# VNT_Controller_Schematic.net
KiCad netlist of a schematic drawn in EAGLE
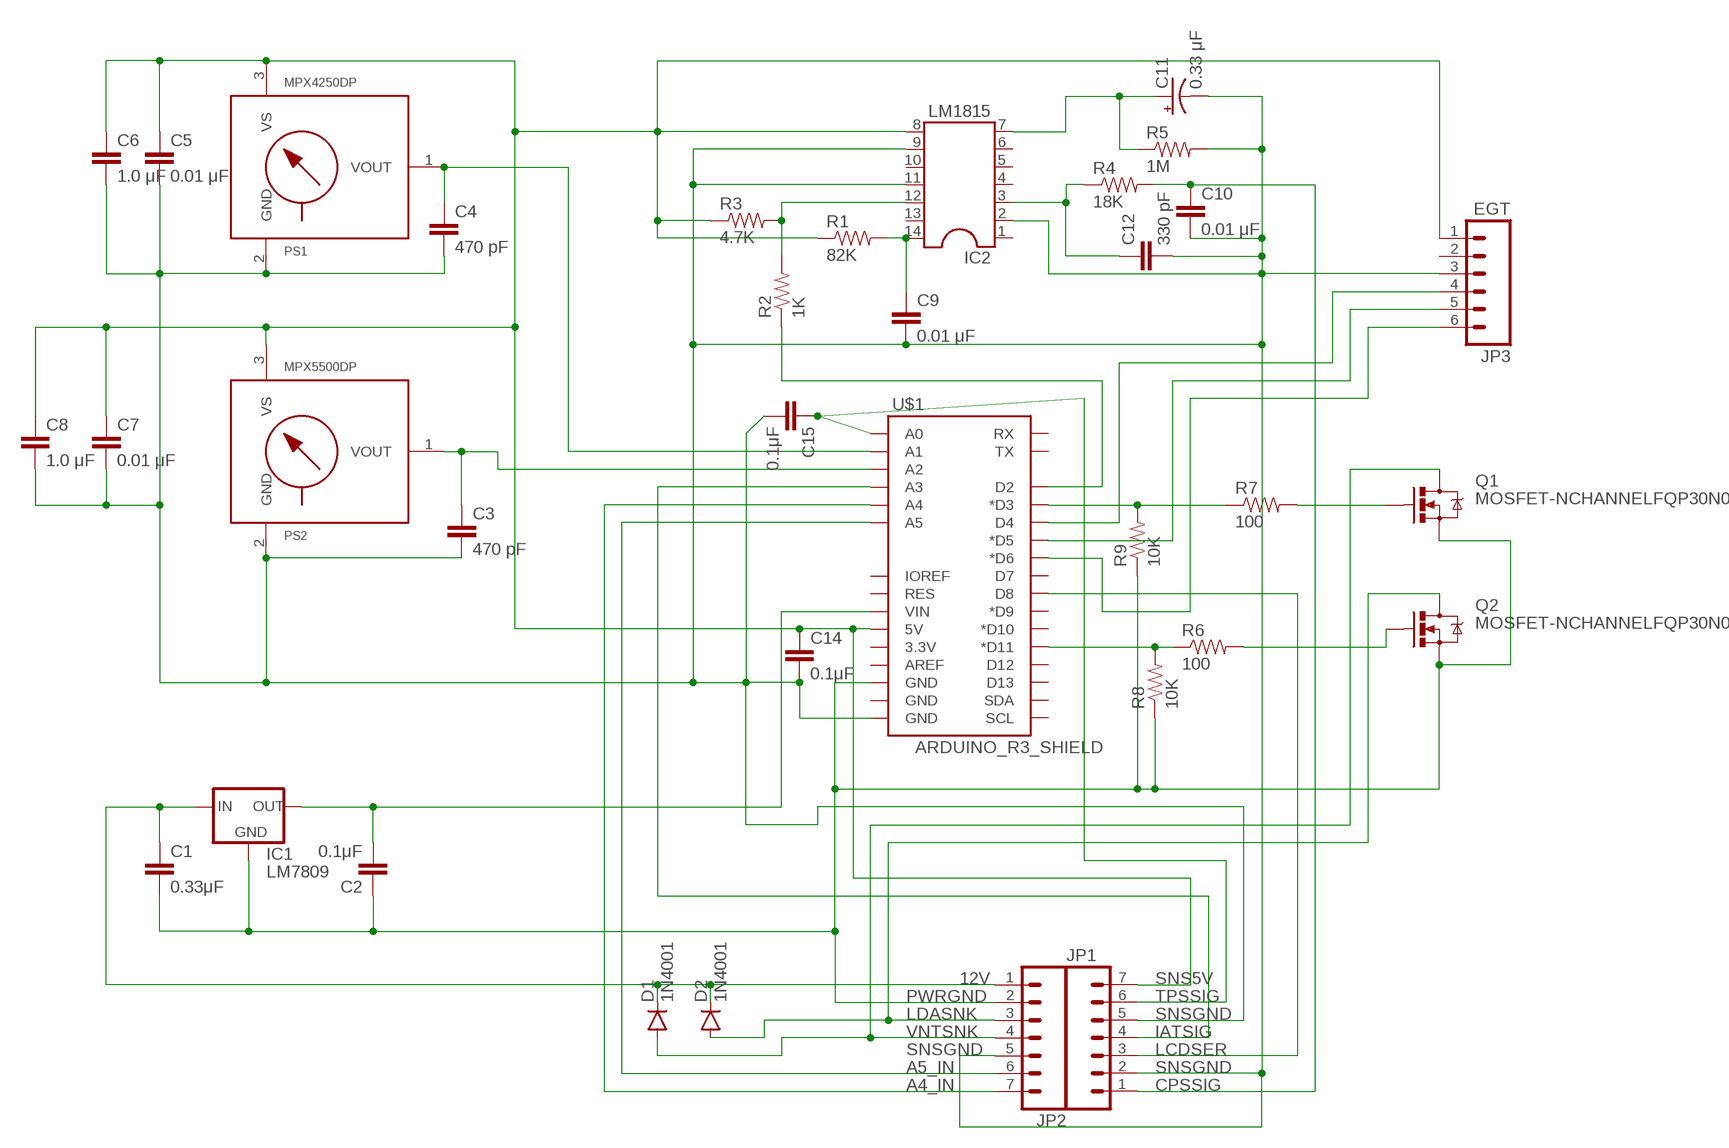
[diagram p0: schematic, sheet 1]

(export (version "E")
  (design (tool "Eeschema 10.0.6"))
  (components
    (comp (ref "C1")
      (value "0.33μF")
      (footprint "eagle-import:CAP-PTH-SMALL")
      (libsource (lib "eagle-import") (part "CAPPTH"))
    )
    (comp (ref "C2")
      (value "0.1μF")
      (footprint "eagle-import:CAP-PTH-SMALL")
      (libsource (lib "eagle-import") (part "CAPPTH"))
    )
    (comp (ref "C3")
      (value "470 pF")
      (footprint "eagle-import:CAP-PTH-SMALL")
      (libsource (lib "eagle-import") (part "CAPPTH"))
    )
    (comp (ref "C4")
      (value "470 pF")
      (footprint "eagle-import:CAP-PTH-SMALL")
      (libsource (lib "eagle-import") (part "CAPPTH"))
    )
    (comp (ref "C5")
      (value "0.01 μF")
      (footprint "eagle-import:CAP-PTH-SMALL")
      (libsource (lib "eagle-import") (part "CAPPTH"))
    )
    (comp (ref "C6")
      (value "1.0 μF")
      (footprint "eagle-import:CAP-PTH-SMALL")
      (libsource (lib "eagle-import") (part "CAPPTH"))
    )
    (comp (ref "C7")
      (value "0.01 μF")
      (footprint "eagle-import:CAP-PTH-SMALL")
      (libsource (lib "eagle-import") (part "CAPPTH"))
    )
    (comp (ref "C8")
      (value "1.0 μF")
      (footprint "eagle-import:CAP-PTH-SMALL")
      (libsource (lib "eagle-import") (part "CAPPTH"))
    )
    (comp (ref "C9")
      (value "0.01 μF")
      (footprint "eagle-import:CAP-PTH-SMALL")
      (libsource (lib "eagle-import") (part "CAPPTH"))
    )
    (comp (ref "C10")
      (value "0.01 μF")
      (footprint "eagle-import:CAP-PTH-SMALL")
      (libsource (lib "eagle-import") (part "CAPPTH"))
    )
    (comp (ref "C11")
      (value "0.33 μF")
      (footprint "eagle-import:CPOL-RADIAL-10UF-25V")
      (libsource (lib "eagle-import") (part "CAP_POLPTH2"))
    )
    (comp (ref "C12")
      (value "330 pF")
      (footprint "eagle-import:CAP-PTH-SMALL")
      (libsource (lib "eagle-import") (part "CAPPTH"))
    )
    (comp (ref "C14")
      (value "0.1μF")
      (footprint "eagle-import:CAP-PTH-SMALL")
      (libsource (lib "eagle-import") (part "CAPPTH"))
    )
    (comp (ref "C15")
      (value "0.1μF")
      (footprint "eagle-import:CAP-PTH-SMALL")
      (libsource (lib "eagle-import") (part "CAPPTH"))
    )
    (comp (ref "D1")
      (value "1N4001")
      (footprint "eagle-import:DIODE-1N4001")
      (libsource (lib "eagle-import") (part "DIODEPTH"))
    )
    (comp (ref "D2")
      (value "1N4001")
      (footprint "eagle-import:DIODE-1N4001")
      (libsource (lib "eagle-import") (part "DIODEPTH"))
    )
    (comp (ref "IC1")
      (value "LM7809")
      (footprint "eagle-import:TO220-IGO")
      (libsource (lib "eagle-import") (part "V_REG_78XXSINK"))
    )
    (comp (ref "IC2")
      (value "LM1815")
      (footprint "eagle-import:SOCKET-14")
      (libsource (lib "eagle-import") (part "DIL14S"))
    )
    (comp (ref "JP1")
      (value "M07LOCK_LONGPADS")
      (footprint "eagle-import:1X07_LOCK_LONGPADS")
      (libsource (lib "eagle-import") (part "M07LOCK_LONGPADS"))
    )
    (comp (ref "JP2")
      (value "M07LOCK_LONGPADS")
      (footprint "eagle-import:1X07_LOCK_LONGPADS")
      (libsource (lib "eagle-import") (part "M07LOCK_LONGPADS"))
    )
    (comp (ref "JP3")
      (value "EGT")
      (footprint "eagle-import:1X06-SIP_LOCK")
      (libsource (lib "eagle-import") (part "M06SIP_LOCK"))
    )
    (comp (ref "PS1")
      (value "MPX4250DP")
      (footprint "eagle-import:867C-H")
      (libsource (lib "eagle-import") (part "MPX-867C-H"))
    )
    (comp (ref "PS2")
      (value "MPX5500DP")
      (footprint "eagle-import:867C-H")
      (libsource (lib "eagle-import") (part "MPX-867C-H"))
    )
    (comp (ref "Q1")
      (value "MOSFET-NCHANNELFQP30N06L")
      (footprint "eagle-import:TO220V")
      (libsource (lib "eagle-import") (part "MOSFET-NCHANNELFQP30N06L"))
    )
    (comp (ref "Q2")
      (value "MOSFET-NCHANNELFQP30N06L")
      (footprint "eagle-import:TO220V")
      (libsource (lib "eagle-import") (part "MOSFET-NCHANNELFQP30N06L"))
    )
    (comp (ref "R1")
      (value "82K")
      (footprint "eagle-import:AXIAL-0.1")
      (libsource (lib "eagle-import") (part "RESISTORPTH-1/4W-VERT"))
    )
    (comp (ref "R2")
      (value "1K")
      (footprint "eagle-import:AXIAL-0.1")
      (libsource (lib "eagle-import") (part "RESISTORPTH-1/4W-VERT"))
    )
    (comp (ref "R3")
      (value "4.7K")
      (footprint "eagle-import:AXIAL-0.1")
      (libsource (lib "eagle-import") (part "RESISTORPTH-1/4W-VERT"))
    )
    (comp (ref "R4")
      (value "18K")
      (footprint "eagle-import:AXIAL-0.1")
      (libsource (lib "eagle-import") (part "RESISTORPTH-1/4W-VERT"))
    )
    (comp (ref "R5")
      (value "1M")
      (footprint "eagle-import:AXIAL-0.1")
      (libsource (lib "eagle-import") (part "RESISTORPTH-1/4W-VERT"))
    )
    (comp (ref "R6")
      (value "100")
      (footprint "eagle-import:AXIAL-0.1")
      (libsource (lib "eagle-import") (part "RESISTORPTH-1/4W-VERT"))
    )
    (comp (ref "R7")
      (value "100")
      (footprint "eagle-import:AXIAL-0.1")
      (libsource (lib "eagle-import") (part "RESISTORPTH-1/4W-VERT"))
    )
    (comp (ref "R8")
      (value "10K")
      (footprint "eagle-import:AXIAL-0.1")
      (libsource (lib "eagle-import") (part "RESISTORPTH-1/4W-VERT"))
    )
    (comp (ref "R9")
      (value "10K")
      (footprint "eagle-import:AXIAL-0.1")
      (libsource (lib "eagle-import") (part "RESISTORPTH-1/4W-VERT"))
    )
    (comp (ref "U$1")
      (value "ARDUINO_R3_SHIELD")
      (footprint "eagle-import:UNO_R3_SHIELD")
      (libsource (lib "eagle-import") (part "ARDUINO_R3_SHIELD"))
    )
  )
  (nets
    (net (code "1") (name "/12V") (class "Default")
      (node (ref "C1") (pin "1") (pinfunction "1_1") (pintype "passive"))
      (node (ref "D1") (pin "C") (pinfunction "C_C") (pintype "passive"))
      (node (ref "D2") (pin "C") (pinfunction "C_C") (pintype "passive"))
      (node (ref "IC1") (pin "IN") (pinfunction "IN_IN") (pintype "input"))
      (node (ref "JP2") (pin "1") (pinfunction "1_1") (pintype "passive"))
    )
    (net (code "2") (name "/A4_IN") (class "Default")
      (node (ref "JP2") (pin "7") (pinfunction "7_7") (pintype "passive"))
      (node (ref "U$1") (pin "A4") (pinfunction "A4_A4") (pintype "bidirectional"))
    )
    (net (code "3") (name "/A5_IN") (class "Default")
      (node (ref "JP2") (pin "6") (pinfunction "6_6") (pintype "passive"))
      (node (ref "U$1") (pin "A5") (pinfunction "A5_A5") (pintype "bidirectional"))
    )
    (net (code "4") (name "/CPSSIG") (class "Default")
      (node (ref "C10") (pin "1") (pinfunction "1_1") (pintype "passive"))
      (node (ref "JP1") (pin "1") (pinfunction "1_1") (pintype "passive"))
      (node (ref "R4") (pin "P$2") (pinfunction "2_P$2") (pintype "passive"))
    )
    (net (code "5") (name "/IATSIG") (class "Default")
      (node (ref "JP1") (pin "4") (pinfunction "4_4") (pintype "passive"))
      (node (ref "U$1") (pin "A3") (pinfunction "A3_A3") (pintype "bidirectional"))
    )
    (net (code "6") (name "/LCDSER") (class "Default")
      (node (ref "JP1") (pin "3") (pinfunction "3_3") (pintype "passive"))
      (node (ref "U$1") (pin "D8") (pinfunction "D8_D8") (pintype "bidirectional"))
    )
    (net (code "7") (name "/LDASNK") (class "Default")
      (node (ref "D2") (pin "A") (pinfunction "A_A") (pintype "passive"))
      (node (ref "JP2") (pin "3") (pinfunction "3_3") (pintype "passive"))
      (node (ref "Q2") (pin "2") (pinfunction "D_2") (pintype "passive"))
    )
    (net (code "8") (name "/PWRGND") (class "Default")
      (node (ref "C1") (pin "2") (pinfunction "2_2") (pintype "passive"))
      (node (ref "C2") (pin "1") (pinfunction "1_1") (pintype "passive"))
      (node (ref "IC1") (pin "GND") (pinfunction "GND_GND") (pintype "input"))
      (node (ref "JP2") (pin "2") (pinfunction "2_2") (pintype "passive"))
      (node (ref "Q1") (pin "3") (pinfunction "S_3") (pintype "passive"))
      (node (ref "Q2") (pin "3") (pinfunction "S_3") (pintype "passive"))
      (node (ref "R8") (pin "P$1") (pinfunction "1_P$1") (pintype "passive"))
      (node (ref "R9") (pin "P$1") (pinfunction "1_P$1") (pintype "passive"))
      (node (ref "U$1") (pin "GND@2") (pinfunction "GND_GND@2") (pintype "bidirectional"))
    )
    (net (code "9") (name "/SNS5V") (class "Default")
      (node (ref "C14") (pin "1") (pinfunction "1_1") (pintype "passive"))
      (node (ref "C5") (pin "1") (pinfunction "1_1") (pintype "passive"))
      (node (ref "C6") (pin "1") (pinfunction "1_1") (pintype "passive"))
      (node (ref "C7") (pin "1") (pinfunction "1_1") (pintype "passive"))
      (node (ref "C8") (pin "1") (pinfunction "1_1") (pintype "passive"))
      (node (ref "IC2") (pin "8") (pinfunction "8_8") (pintype "passive"))
      (node (ref "JP1") (pin "7") (pinfunction "7_7") (pintype "passive"))
      (node (ref "JP3") (pin "1") (pinfunction "1_1") (pintype "passive"))
      (node (ref "PS1") (pin "3") (pinfunction "VS_3") (pintype "power_in"))
      (node (ref "PS2") (pin "3") (pinfunction "VS_3") (pintype "power_in"))
      (node (ref "R1") (pin "P$1") (pinfunction "1_P$1") (pintype "passive"))
      (node (ref "R3") (pin "P$1") (pinfunction "1_P$1") (pintype "passive"))
      (node (ref "U$1") (pin "5V") (pinfunction "5V_5V") (pintype "bidirectional"))
    )
    (net (code "10") (name "/SNSGND") (class "Default")
      (node (ref "C10") (pin "2") (pinfunction "2_2") (pintype "passive"))
      (node (ref "C11") (pin "2") (pinfunction "-_2") (pintype "passive"))
      (node (ref "C12") (pin "2") (pinfunction "2_2") (pintype "passive"))
      (node (ref "C14") (pin "2") (pinfunction "2_2") (pintype "passive"))
      (node (ref "C15") (pin "2") (pinfunction "2_2") (pintype "passive"))
      (node (ref "C3") (pin "2") (pinfunction "2_2") (pintype "passive"))
      (node (ref "C4") (pin "2") (pinfunction "2_2") (pintype "passive"))
      (node (ref "C5") (pin "2") (pinfunction "2_2") (pintype "passive"))
      (node (ref "C6") (pin "2") (pinfunction "2_2") (pintype "passive"))
      (node (ref "C7") (pin "2") (pinfunction "2_2") (pintype "passive"))
      (node (ref "C8") (pin "2") (pinfunction "2_2") (pintype "passive"))
      (node (ref "C9") (pin "2") (pinfunction "2_2") (pintype "passive"))
      (node (ref "IC2") (pin "11") (pinfunction "11_11") (pintype "passive"))
      (node (ref "IC2") (pin "2") (pinfunction "2_2") (pintype "passive"))
      (node (ref "IC2") (pin "9") (pinfunction "9_9") (pintype "passive"))
      (node (ref "JP1") (pin "2") (pinfunction "2_2") (pintype "passive"))
      (node (ref "JP1") (pin "5") (pinfunction "5_5") (pintype "passive"))
      (node (ref "JP2") (pin "5") (pinfunction "5_5") (pintype "passive"))
      (node (ref "JP3") (pin "3") (pinfunction "3_3") (pintype "passive"))
      (node (ref "PS1") (pin "2") (pinfunction "GND_2") (pintype "power_in"))
      (node (ref "PS2") (pin "2") (pinfunction "GND_2") (pintype "power_in"))
      (node (ref "R5") (pin "P$2") (pinfunction "2_P$2") (pintype "passive"))
      (node (ref "U$1") (pin "GND@0") (pinfunction "GND_GND@0") (pintype "bidirectional"))
    )
    (net (code "11") (name "/TPSSIG") (class "Default")
      (node (ref "C15") (pin "1") (pinfunction "1_1") (pintype "passive"))
      (node (ref "JP1") (pin "6") (pinfunction "6_6") (pintype "passive"))
      (node (ref "U$1") (pin "A0") (pinfunction "A0_A0") (pintype "bidirectional"))
    )
    (net (code "12") (name "/VNTSNK") (class "Default")
      (node (ref "D1") (pin "A") (pinfunction "A_A") (pintype "passive"))
      (node (ref "JP2") (pin "4") (pinfunction "4_4") (pintype "passive"))
      (node (ref "Q1") (pin "2") (pinfunction "D_2") (pintype "passive"))
    )
    (net (code "13") (name "Net-(C2-Pad2)") (class "Default")
      (node (ref "C2") (pin "2") (pinfunction "2_2") (pintype "passive"))
      (node (ref "IC1") (pin "OUT") (pinfunction "OUT_OUT") (pintype "output"))
      (node (ref "U$1") (pin "VIN") (pinfunction "VIN_VIN") (pintype "bidirectional"))
    )
    (net (code "14") (name "Net-(C11-+)") (class "Default")
      (node (ref "C11") (pin "1") (pinfunction "+_1") (pintype "passive"))
      (node (ref "IC2") (pin "7") (pinfunction "7_7") (pintype "passive"))
      (node (ref "R5") (pin "P$1") (pinfunction "1_P$1") (pintype "passive"))
    )
    (net (code "15") (name "Net-(JP3-Pad4)") (class "Default")
      (node (ref "JP3") (pin "4") (pinfunction "4_4") (pintype "passive"))
      (node (ref "U$1") (pin "D4") (pinfunction "D4_D4") (pintype "bidirectional"))
    )
    (net (code "16") (name "Net-(PS1-VOUT)") (class "Default")
      (node (ref "C4") (pin "1") (pinfunction "1_1") (pintype "passive"))
      (node (ref "PS1") (pin "1") (pinfunction "VOUT_1") (pintype "output"))
      (node (ref "U$1") (pin "A1") (pinfunction "A1_A1") (pintype "bidirectional"))
    )
    (net (code "17") (name "Net-(PS2-VOUT)") (class "Default")
      (node (ref "C3") (pin "1") (pinfunction "1_1") (pintype "passive"))
      (node (ref "PS2") (pin "1") (pinfunction "VOUT_1") (pintype "output"))
      (node (ref "U$1") (pin "A2") (pinfunction "A2_A2") (pintype "bidirectional"))
    )
    (net (code "18") (name "Net-(Q1-G)") (class "Default")
      (node (ref "Q1") (pin "1") (pinfunction "G_1") (pintype "passive"))
      (node (ref "R7") (pin "P$2") (pinfunction "2_P$2") (pintype "passive"))
    )
    (net (code "19") (name "Net-(Q2-G)") (class "Default")
      (node (ref "Q2") (pin "1") (pinfunction "G_1") (pintype "passive"))
      (node (ref "R6") (pin "P$2") (pinfunction "2_P$2") (pintype "passive"))
    )
    (net (code "20") (name "Net-(R1-2)") (class "Default")
      (node (ref "C9") (pin "1") (pinfunction "1_1") (pintype "passive"))
      (node (ref "IC2") (pin "14") (pinfunction "14_14") (pintype "passive"))
      (node (ref "R1") (pin "P$2") (pinfunction "2_P$2") (pintype "passive"))
    )
    (net (code "21") (name "Net-(R2-1)") (class "Default")
      (node (ref "R2") (pin "P$1") (pinfunction "1_P$1") (pintype "passive"))
      (node (ref "U$1") (pin "D2") (pinfunction "D2_D2") (pintype "bidirectional"))
    )
    (net (code "22") (name "Net-(R2-2)") (class "Default")
      (node (ref "IC2") (pin "12") (pinfunction "12_12") (pintype "passive"))
      (node (ref "R2") (pin "P$2") (pinfunction "2_P$2") (pintype "passive"))
      (node (ref "R3") (pin "P$2") (pinfunction "2_P$2") (pintype "passive"))
    )
    (net (code "23") (name "Net-(R4-1)") (class "Default")
      (node (ref "C12") (pin "1") (pinfunction "1_1") (pintype "passive"))
      (node (ref "IC2") (pin "3") (pinfunction "3_3") (pintype "passive"))
      (node (ref "R4") (pin "P$1") (pinfunction "1_P$1") (pintype "passive"))
    )
    (net (code "24") (name "Net-(R6-1)") (class "Default")
      (node (ref "R6") (pin "P$1") (pinfunction "1_P$1") (pintype "passive"))
      (node (ref "R8") (pin "P$2") (pinfunction "2_P$2") (pintype "passive"))
      (node (ref "U$1") (pin "D11") (pinfunction "*D11_D11") (pintype "bidirectional"))
    )
    (net (code "25") (name "Net-(R7-1)") (class "Default")
      (node (ref "R7") (pin "P$1") (pinfunction "1_P$1") (pintype "passive"))
      (node (ref "R9") (pin "P$2") (pinfunction "2_P$2") (pintype "passive"))
      (node (ref "U$1") (pin "D3") (pinfunction "*D3_D3") (pintype "bidirectional"))
    )
    (net (code "26") (name "Net-(U$1-*D5)") (class "Default")
      (node (ref "JP3") (pin "5") (pinfunction "5_5") (pintype "passive"))
      (node (ref "U$1") (pin "D5") (pinfunction "*D5_D5") (pintype "bidirectional"))
    )
    (net (code "27") (name "Net-(U$1-*D6)") (class "Default")
      (node (ref "JP3") (pin "6") (pinfunction "6_6") (pintype "passive"))
      (node (ref "U$1") (pin "D6") (pinfunction "*D6_D6") (pintype "bidirectional"))
    )
    (net (code "28") (name "unconnected-(IC2-Pad1)") (class "Default")
      (node (ref "IC2") (pin "1") (pinfunction "1_1") (pintype "passive"))
    )
    (net (code "29") (name "unconnected-(IC2-Pad4)") (class "Default")
      (node (ref "IC2") (pin "4") (pinfunction "4_4") (pintype "passive"))
    )
    (net (code "30") (name "unconnected-(IC2-Pad5)") (class "Default")
      (node (ref "IC2") (pin "5") (pinfunction "5_5") (pintype "passive"))
    )
    (net (code "31") (name "unconnected-(IC2-Pad6)") (class "Default")
      (node (ref "IC2") (pin "6") (pinfunction "6_6") (pintype "passive"))
    )
    (net (code "32") (name "unconnected-(IC2-Pad10)") (class "Default")
      (node (ref "IC2") (pin "10") (pinfunction "10_10") (pintype "passive"))
    )
    (net (code "33") (name "unconnected-(IC2-Pad13)") (class "Default")
      (node (ref "IC2") (pin "13") (pinfunction "13_13") (pintype "passive"))
    )
    (net (code "34") (name "unconnected-(JP3-Pad2)") (class "Default")
      (node (ref "JP3") (pin "2") (pinfunction "2_2") (pintype "passive"))
    )
    (net (code "35") (name "unconnected-(PS1-NC-Pad4)") (class "Default")
      (node (ref "PS1") (pin "4") (pinfunction "NC_4") (pintype "no_connect"))
    )
    (net (code "36") (name "unconnected-(PS1-NC-Pad5)") (class "Default")
      (node (ref "PS1") (pin "5") (pinfunction "NC_5") (pintype "no_connect"))
    )
    (net (code "37") (name "unconnected-(PS1-NC-Pad6)") (class "Default")
      (node (ref "PS1") (pin "6") (pinfunction "NC_6") (pintype "no_connect"))
    )
    (net (code "38") (name "unconnected-(PS2-NC-Pad4)") (class "Default")
      (node (ref "PS2") (pin "4") (pinfunction "NC_4") (pintype "no_connect"))
    )
    (net (code "39") (name "unconnected-(PS2-NC-Pad5)") (class "Default")
      (node (ref "PS2") (pin "5") (pinfunction "NC_5") (pintype "no_connect"))
    )
    (net (code "40") (name "unconnected-(PS2-NC-Pad6)") (class "Default")
      (node (ref "PS2") (pin "6") (pinfunction "NC_6") (pintype "no_connect"))
    )
    (net (code "41") (name "unconnected-(U$1-*D9-PadD9)") (class "Default")
      (node (ref "U$1") (pin "D9") (pinfunction "*D9_D9") (pintype "bidirectional"))
    )
    (net (code "42") (name "unconnected-(U$1-*D10-PadD10)") (class "Default")
      (node (ref "U$1") (pin "D10") (pinfunction "*D10_D10") (pintype "bidirectional"))
    )
    (net (code "43") (name "unconnected-(U$1-GND-PadGND@1)") (class "Default")
      (node (ref "U$1") (pin "GND@1") (pinfunction "GND_GND@1") (pintype "bidirectional"))
    )
    (net (code "44") (name "unconnected-(U$1-Pad3.3V)") (class "Default")
      (node (ref "U$1") (pin "3.3V") (pinfunction "3.3V_3.3V") (pintype "bidirectional"))
    )
    (net (code "45") (name "unconnected-(U$1-PadAREF)") (class "Default")
      (node (ref "U$1") (pin "AREF") (pinfunction "AREF_AREF") (pintype "bidirectional"))
    )
    (net (code "46") (name "unconnected-(U$1-PadD7)") (class "Default")
      (node (ref "U$1") (pin "D7") (pinfunction "D7_D7") (pintype "bidirectional"))
    )
    (net (code "47") (name "unconnected-(U$1-PadD12)") (class "Default")
      (node (ref "U$1") (pin "D12") (pinfunction "D12_D12") (pintype "bidirectional"))
    )
    (net (code "48") (name "unconnected-(U$1-PadD13)") (class "Default")
      (node (ref "U$1") (pin "D13") (pinfunction "D13_D13") (pintype "bidirectional"))
    )
    (net (code "49") (name "unconnected-(U$1-PadIOREF)") (class "Default")
      (node (ref "U$1") (pin "IOREF") (pinfunction "IOREF_IOREF") (pintype "bidirectional"))
    )
    (net (code "50") (name "unconnected-(U$1-PadRES)") (class "Default")
      (node (ref "U$1") (pin "RES") (pinfunction "RES_RES") (pintype "bidirectional"))
    )
    (net (code "51") (name "unconnected-(U$1-PadRX)") (class "Default")
      (node (ref "U$1") (pin "RX") (pinfunction "RX_RX") (pintype "bidirectional"))
    )
    (net (code "52") (name "unconnected-(U$1-PadSCL)") (class "Default")
      (node (ref "U$1") (pin "SCL") (pinfunction "SCL_SCL") (pintype "bidirectional"))
    )
    (net (code "53") (name "unconnected-(U$1-PadSDA)") (class "Default")
      (node (ref "U$1") (pin "SDA") (pinfunction "SDA_SDA") (pintype "bidirectional"))
    )
    (net (code "54") (name "unconnected-(U$1-PadTX)") (class "Default")
      (node (ref "U$1") (pin "TX") (pinfunction "TX_TX") (pintype "bidirectional"))
    )
  )
)
